# FabOptimusEdited.net
KiCad netlist of a schematic drawn in EAGLE
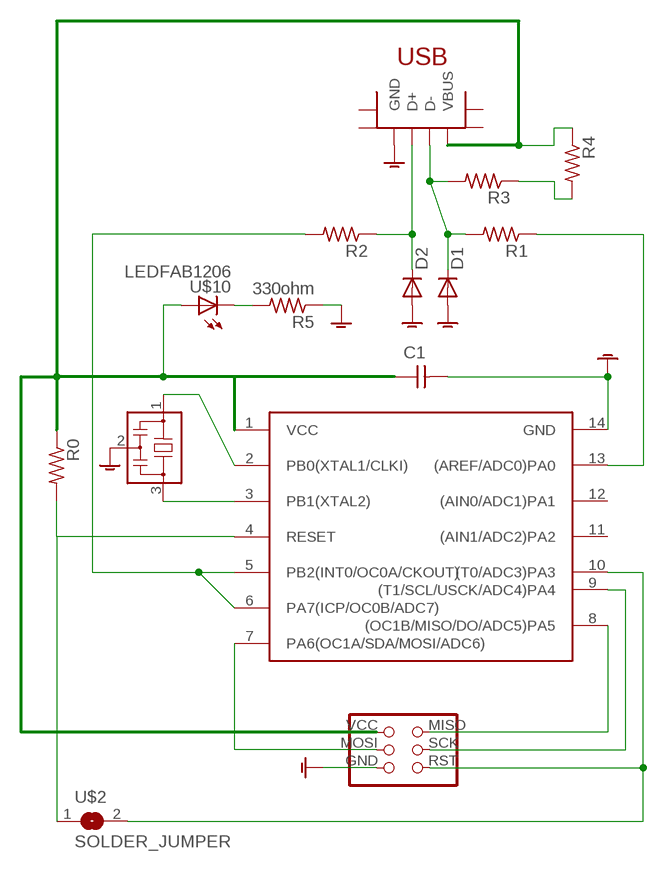
[diagram p0: schematic, sheet 1]

(export (version "E")
  (design (tool "Eeschema 10.0.6"))
  (components
    (comp (ref "C1")
      (value "CAP-UNPOLARIZEDFAB")
      (footprint "eagle-import:C1206FAB")
      (libsource (lib "eagle-import") (part "CAP-UNPOLARIZEDFAB"))
    )
    (comp (ref "D1")
      (value "DIODESOD123")
      (footprint "eagle-import:SOD123")
      (libsource (lib "eagle-import") (part "DIODESOD123"))
    )
    (comp (ref "D2")
      (value "DIODESOD123")
      (footprint "eagle-import:SOD123")
      (libsource (lib "eagle-import") (part "DIODESOD123"))
    )
    (comp (ref "IC1")
      (value "ATTINY44-SSU")
      (footprint "eagle-import:SOIC14_ATTTINY44")
      (libsource (lib "eagle-import") (part "ATTINY44-SSU"))
    )
    (comp (ref "JP1")
      (value "2X3PINHEADER")
      (footprint "eagle-import:2X3PINHEADER")
      (libsource (lib "eagle-import") (part "2X3PINHEADER"))
    )
    (comp (ref "R0")
      (value "RES-US1206FAB")
      (footprint "eagle-import:R1206FAB")
      (libsource (lib "eagle-import") (part "RES-US1206FAB"))
    )
    (comp (ref "R1")
      (value "RES-US1206FAB")
      (footprint "eagle-import:R1206FAB")
      (libsource (lib "eagle-import") (part "RES-US1206FAB"))
    )
    (comp (ref "R2")
      (value "RES-US1206FAB")
      (footprint "eagle-import:R1206FAB")
      (libsource (lib "eagle-import") (part "RES-US1206FAB"))
    )
    (comp (ref "R3")
      (value "RES-US1206FAB")
      (footprint "eagle-import:R1206FAB")
      (libsource (lib "eagle-import") (part "RES-US1206FAB"))
    )
    (comp (ref "R4")
      (value "RES-US1206FAB")
      (footprint "eagle-import:R1206FAB")
      (libsource (lib "eagle-import") (part "RES-US1206FAB"))
    )
    (comp (ref "R5")
      (value "330ohm")
      (footprint "eagle-import:R1206FAB")
      (libsource (lib "eagle-import") (part "RES-US1206FAB"))
    )
    (comp (ref "U$1")
      (value "RESONATOR")
      (footprint "eagle-import:EFOBM")
      (libsource (lib "eagle-import") (part "RESONATOR"))
    )
    (comp (ref "U$2")
      (value "SOLDER_JUMPER")
      (footprint "eagle-import:SOLDERJUMPER")
      (libsource (lib "eagle-import") (part "SOLDER_JUMPER"))
    )
    (comp (ref "U$8")
      (value "USB_MINIB")
      (footprint "eagle-import:USB_MINIB")
      (libsource (lib "eagle-import") (part "USB_MINIB"))
    )
    (comp (ref "U$10")
      (value "LEDFAB1206")
      (footprint "eagle-import:LED1206FAB")
      (libsource (lib "eagle-import") (part "LEDFAB1206"))
    )
  )
  (nets
    (net (code "1") (name "GND") (class "Default")
      (node (ref "C1") (pin "2") (pinfunction "2_2") (pintype "passive"))
      (node (ref "D1") (pin "ANODE") (pinfunction "A_ANODE") (pintype "passive"))
      (node (ref "D2") (pin "ANODE") (pinfunction "A_ANODE") (pintype "passive"))
      (node (ref "IC1") (pin "14") (pinfunction "GND_14") (pintype "power_in"))
      (node (ref "JP1") (pin "GND") (pinfunction "1_GND") (pintype "passive"))
      (node (ref "R5") (pin "1") (pinfunction "1_1") (pintype "passive"))
      (node (ref "U$1") (pin "2") (pinfunction "2_2") (pintype "passive"))
      (node (ref "U$8") (pin "GND") (pinfunction "GND_GND") (pintype "bidirectional"))
    )
    (net (code "2") (name "Net-(D1-C)") (class "Default")
      (node (ref "D1") (pin "CATHODE") (pinfunction "C_CATHODE") (pintype "passive"))
      (node (ref "R1") (pin "2") (pinfunction "2_2") (pintype "passive"))
      (node (ref "R3") (pin "2") (pinfunction "2_2") (pintype "passive"))
      (node (ref "U$8") (pin "D-") (pinfunction "D-_D-") (pintype "bidirectional"))
    )
    (net (code "3") (name "Net-(D2-C)") (class "Default")
      (node (ref "D2") (pin "CATHODE") (pinfunction "C_CATHODE") (pintype "passive"))
      (node (ref "R2") (pin "1") (pinfunction "1_1") (pintype "passive"))
      (node (ref "U$8") (pin "D+") (pinfunction "D+_D+") (pintype "bidirectional"))
    )
    (net (code "4") (name "Net-(IC1-(AREF{slash}ADC0)PA0)") (class "Default")
      (node (ref "IC1") (pin "13") (pinfunction "(AREF/ADC0)PA0_13") (pintype "bidirectional"))
      (node (ref "R1") (pin "1") (pinfunction "1_1") (pintype "passive"))
    )
    (net (code "5") (name "Net-(IC1-(OC1B{slash}MISO{slash}DO{slash}ADC5)PA5)") (class "Default")
      (node (ref "IC1") (pin "8") (pinfunction "(OC1B/MISO/DO/ADC5)PA5_8") (pintype "bidirectional"))
      (node (ref "JP1") (pin "MISO") (pinfunction "6_MISO") (pintype "passive"))
    )
    (net (code "6") (name "Net-(IC1-(T0{slash}ADC3)PA3)") (class "Default")
      (node (ref "IC1") (pin "10") (pinfunction "(T0/ADC3)PA3_10") (pintype "bidirectional"))
      (node (ref "JP1") (pin "RST") (pinfunction "2_RST") (pintype "passive"))
      (node (ref "U$2") (pin "2") (pinfunction "2_2") (pintype "passive"))
    )
    (net (code "7") (name "Net-(IC1-(T1{slash}SCL{slash}USCK{slash}ADC4)PA4)") (class "Default")
      (node (ref "IC1") (pin "9") (pinfunction "(T1/SCL/USCK/ADC4)PA4_9") (pintype "bidirectional"))
      (node (ref "JP1") (pin "SCK") (pinfunction "4_SCK") (pintype "passive"))
    )
    (net (code "8") (name "Net-(IC1-PA6(OC1A{slash}SDA{slash}MOSI{slash}ADC6))") (class "Default")
      (node (ref "IC1") (pin "7") (pinfunction "PA6(OC1A/SDA/MOSI/ADC6)_7") (pintype "bidirectional"))
      (node (ref "JP1") (pin "MOSI") (pinfunction "3_MOSI") (pintype "passive"))
    )
    (net (code "9") (name "Net-(IC1-PA7(ICP{slash}OC0B{slash}ADC7))") (class "Default")
      (node (ref "IC1") (pin "5") (pinfunction "PB2(INT0/OC0A/CKOUT)_5") (pintype "bidirectional"))
      (node (ref "IC1") (pin "6") (pinfunction "PA7(ICP/OC0B/ADC7)_6") (pintype "bidirectional"))
      (node (ref "R2") (pin "2") (pinfunction "2_2") (pintype "passive"))
    )
    (net (code "10") (name "Net-(IC1-PB0(XTAL1{slash}CLKI))") (class "Default")
      (node (ref "IC1") (pin "2") (pinfunction "PB0(XTAL1/CLKI)_2") (pintype "bidirectional"))
      (node (ref "U$1") (pin "1") (pinfunction "1_1") (pintype "passive"))
    )
    (net (code "11") (name "Net-(IC1-PB1(XTAL2))") (class "Default")
      (node (ref "IC1") (pin "3") (pinfunction "PB1(XTAL2)_3") (pintype "bidirectional"))
      (node (ref "U$1") (pin "3") (pinfunction "3_3") (pintype "passive"))
    )
    (net (code "12") (name "Net-(IC1-RESET)") (class "Default")
      (node (ref "IC1") (pin "4") (pinfunction "RESET_4") (pintype "bidirectional"))
      (node (ref "R0") (pin "2") (pinfunction "2_2") (pintype "passive"))
      (node (ref "U$2") (pin "1") (pinfunction "1_1") (pintype "passive"))
    )
    (net (code "13") (name "Net-(IC1-VCC)") (class "Default")
      (node (ref "C1") (pin "1") (pinfunction "1_1") (pintype "passive"))
      (node (ref "IC1") (pin "1") (pinfunction "VCC_1") (pintype "power_in"))
      (node (ref "JP1") (pin "VCC") (pinfunction "5_VCC") (pintype "passive"))
      (node (ref "R0") (pin "1") (pinfunction "1_1") (pintype "passive"))
      (node (ref "R4") (pin "1") (pinfunction "1_1") (pintype "passive"))
      (node (ref "U$10") (pin "1") (pinfunction "A_1") (pintype "passive"))
      (node (ref "U$8") (pin "V") (pinfunction "VBUS_V") (pintype "bidirectional"))
    )
    (net (code "14") (name "Net-(R3-Pad1)") (class "Default")
      (node (ref "R3") (pin "1") (pinfunction "1_1") (pintype "passive"))
      (node (ref "R4") (pin "2") (pinfunction "2_2") (pintype "passive"))
    )
    (net (code "15") (name "Net-(U$10-C)") (class "Default")
      (node (ref "R5") (pin "2") (pinfunction "2_2") (pintype "passive"))
      (node (ref "U$10") (pin "2") (pinfunction "C_2") (pintype "passive"))
    )
    (net (code "16") (name "unconnected-(IC1-(AIN0{slash}ADC1)PA1-Pad12)") (class "Default")
      (node (ref "IC1") (pin "12") (pinfunction "(AIN0/ADC1)PA1_12") (pintype "bidirectional"))
    )
    (net (code "17") (name "unconnected-(IC1-(AIN1{slash}ADC2)PA2-Pad11)") (class "Default")
      (node (ref "IC1") (pin "11") (pinfunction "(AIN1/ADC2)PA2_11") (pintype "bidirectional"))
    )
    (net (code "18") (name "unconnected-(U$8-SHIELD-PadSHIELD@1)") (class "Default")
      (node (ref "U$8") (pin "SHIELD@1") (pinfunction "SHIELD_SHIELD@1") (pintype "passive"))
    )
    (net (code "19") (name "unconnected-(U$8-SHIELD1-PadSHIELD@2)") (class "Default")
      (node (ref "U$8") (pin "SHIELD@2") (pinfunction "SHIELD1_SHIELD@2") (pintype "passive"))
    )
    (net (code "20") (name "unconnected-(U$8-SHIELD2-PadSHIELD@3)") (class "Default")
      (node (ref "U$8") (pin "SHIELD@3") (pinfunction "SHIELD2_SHIELD@3") (pintype "passive"))
    )
    (net (code "21") (name "unconnected-(U$8-SHIELD3-PadSHIELD@4)") (class "Default")
      (node (ref "U$8") (pin "SHIELD@4") (pinfunction "SHIELD3_SHIELD@4") (pintype "passive"))
    )
  )
)
